# P_B_Jan_2018.net
KiCad netlist of a schematic drawn in EAGLE
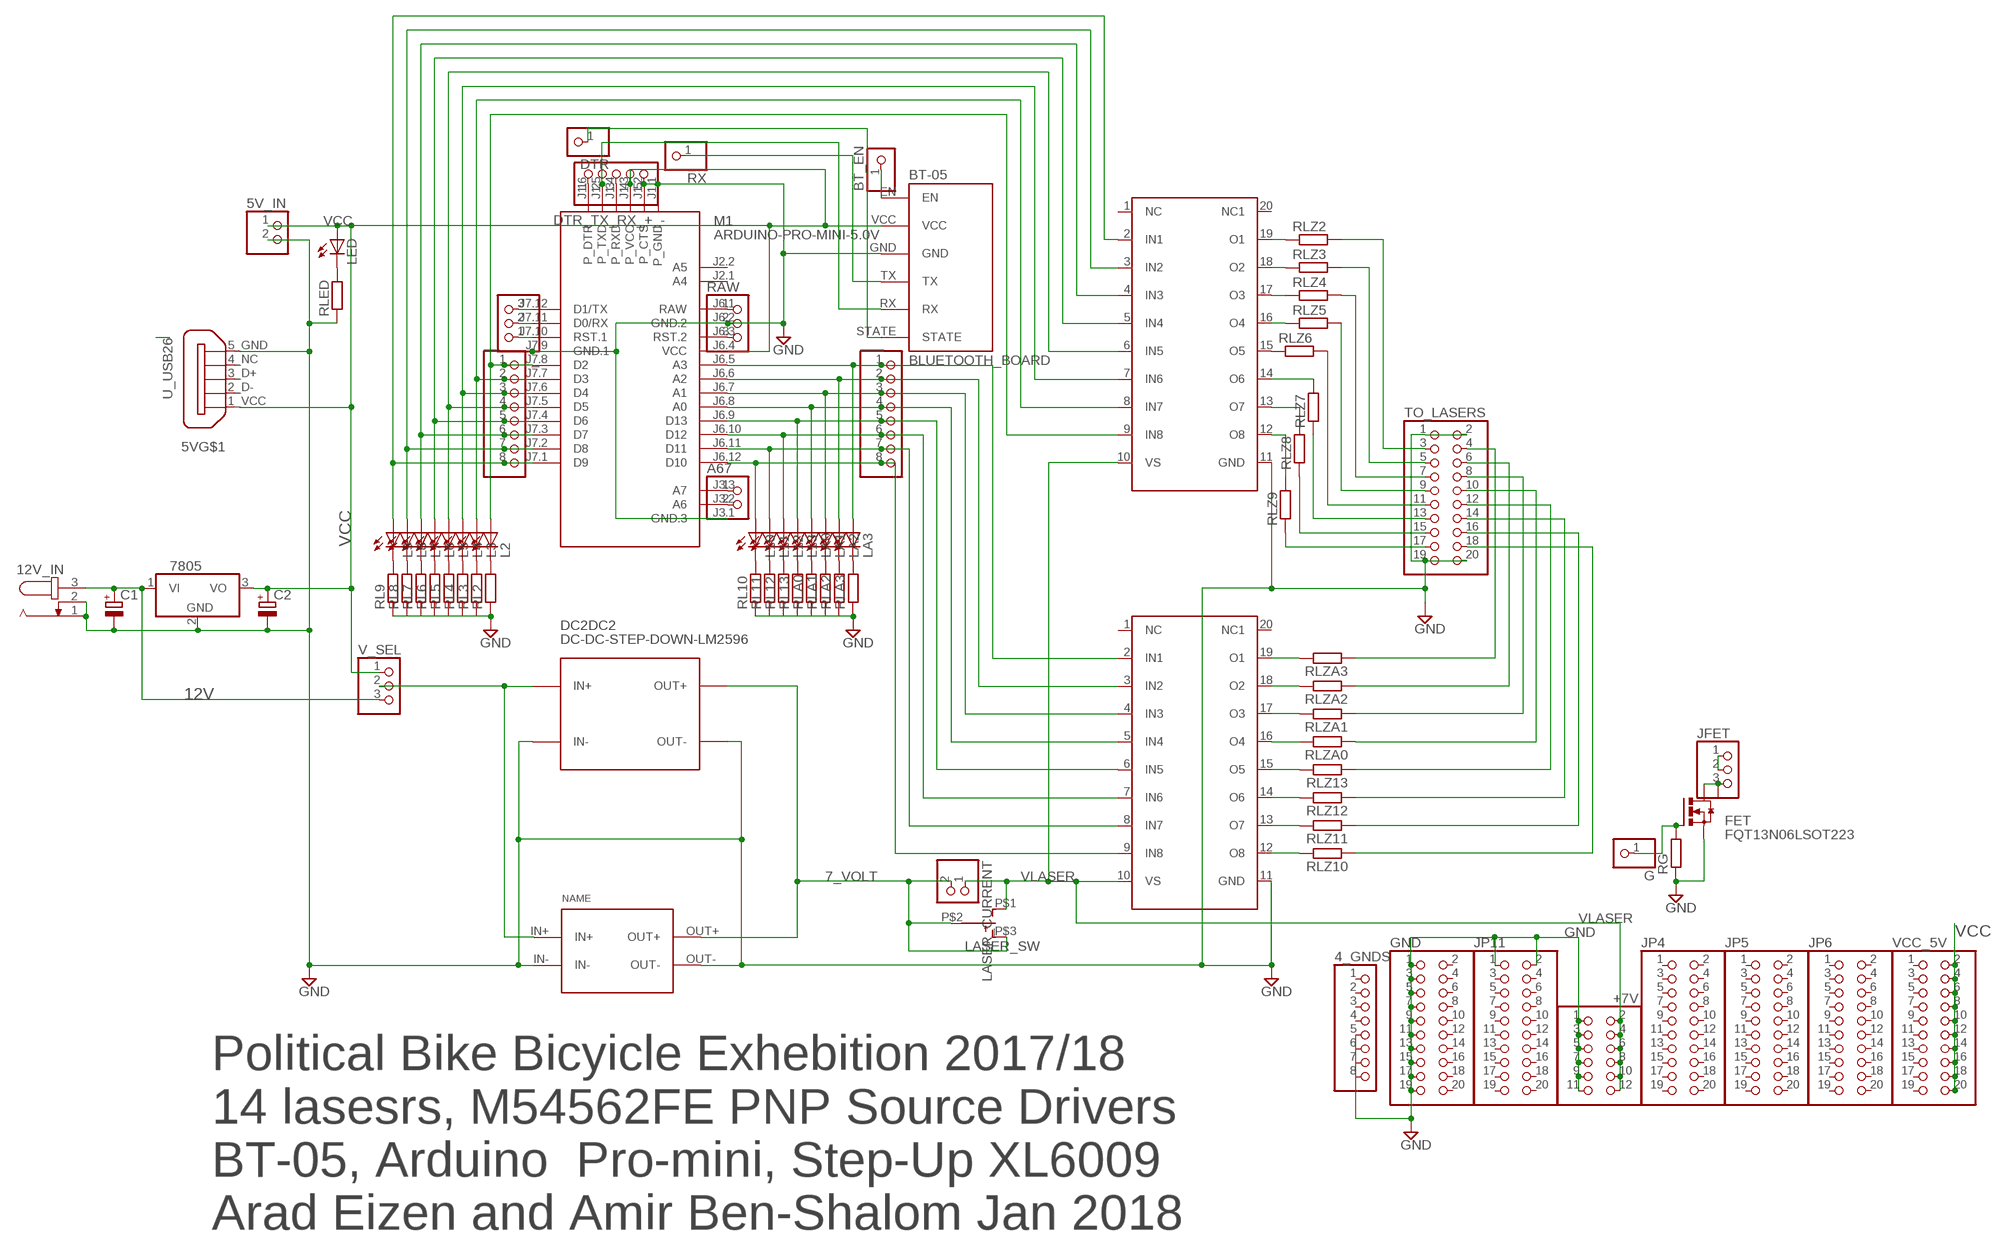
[diagram p0: schematic, sheet 1]

(export (version "E")
  (design (tool "Eeschema 10.0.6"))
  (components
    (comp (ref "+7V")
      (value "PINHD-2X6")
      (footprint "eagle-import:2X06")
      (libsource (lib "eagle-import") (part "PINHD-2X6"))
    )
    (comp (ref "4_GNDS")
      (value "PINHD-1X8")
      (footprint "eagle-import:1X08")
      (libsource (lib "eagle-import") (part "PINHD-1X8"))
    )
    (comp (ref "5V")
      (value "U_USB26")
      (footprint "eagle-import:U_USB_26")
      (libsource (lib "eagle-import") (part "U_USB26"))
    )
    (comp (ref "5V_IN")
      (value "PINHD-1X2SQ&RND")
      (footprint "eagle-import:1X02_SQ&ROUND")
      (libsource (lib "eagle-import") (part "Amir_May_15_for_Copy_only_PINHD-1X2SQ&RND"))
    )
    (comp (ref "12V_IN")
      (value "JACK-PLUGHOLE_PAD")
      (footprint "eagle-import:JACK_DC")
      (libsource (lib "eagle-import") (part "JACK-PLUGHOLE_PAD"))
    )
    (comp (ref "7805")
      (value "7805TV")
      (footprint "eagle-import:TO220V")
      (libsource (lib "eagle-import") (part "78TV05"))
    )
    (comp (ref "A67")
      (value "PINHD-1X2ROUND_PAD")
      (footprint "eagle-import:1X02_ROUND_PAD")
      (libsource (lib "eagle-import") (part "Amir_May_15_for_Copy_only_PINHD-1X2ROUND_PAD"))
    )
    (comp (ref "BT-05")
      (value "BLUETOOTH_BOARD")
      (footprint "eagle-import:BT_BOARD_FOOTPRINT")
      (libsource (lib "eagle-import") (part "BLUETOOTH_BOARD"))
    )
    (comp (ref "BT_EN")
      (value "PINHD-1X1")
      (footprint "eagle-import:1X01")
      (libsource (lib "eagle-import") (part "PINHD-1X1"))
    )
    (comp (ref "C1")
      (value "CPOL-EUE3.5-10")
      (footprint "eagle-import:E3,5-10")
      (libsource (lib "eagle-import") (part "CPOL-EUE3.5-10"))
    )
    (comp (ref "C2")
      (value "CPOL-EUE2.5-6")
      (footprint "eagle-import:E2,5-6")
      (libsource (lib "eagle-import") (part "CPOL-EUE2.5-6"))
    )
    (comp (ref "DC2DC")
      (value "DC2DC_CP8-ADJ")
      (footprint "eagle-import:CP8-ADJ")
      (libsource (lib "eagle-import") (part "DC2DC_CP8-ADJ"))
    )
    (comp (ref "DC2DC2")
      (value "DC-DC-STEP-DOWN-LM2596")
      (footprint "eagle-import:DC-DC-STEP-DOWN-LM2596")
      (libsource (lib "eagle-import") (part "DC-DC-STEP-DOWN-LM2596"))
    )
    (comp (ref "DTR")
      (value "PINHD-1X1")
      (footprint "eagle-import:1X01")
      (libsource (lib "eagle-import") (part "PINHD-1X1"))
    )
    (comp (ref "DTR_TX_RX_+_-")
      (value "PINHD-1X5")
      (footprint "eagle-import:1X05")
      (libsource (lib "eagle-import") (part "PINHD-1X5"))
    )
    (comp (ref "FET")
      (value "FQT13N06LSOT223")
      (footprint "eagle-import:SOT223")
      (libsource (lib "eagle-import") (part "FQT13N06LSOT223"))
    )
    (comp (ref "G")
      (value "PINHD-1X1")
      (footprint "eagle-import:1X01")
      (libsource (lib "eagle-import") (part "PINHD-1X1"))
    )
    (comp (ref "GND")
      (value "PINHD-2X10")
      (footprint "eagle-import:2X10")
      (libsource (lib "eagle-import") (part "PINHD-2X10"))
    )
    (comp (ref "JFET")
      (value "PIN_HEAD_1X3_MARKED2.56")
      (footprint "eagle-import:1X3_MARKED")
      (libsource (lib "eagle-import") (part "PIN_HEAD_1X3_MARKED2.56"))
    )
    (comp (ref "JP4")
      (value "PINHD-2X10")
      (footprint "eagle-import:2X10")
      (libsource (lib "eagle-import") (part "PINHD-2X10"))
    )
    (comp (ref "JP5")
      (value "PINHD-2X10")
      (footprint "eagle-import:2X10")
      (libsource (lib "eagle-import") (part "PINHD-2X10"))
    )
    (comp (ref "JP6")
      (value "PINHD-2X10")
      (footprint "eagle-import:2X10")
      (libsource (lib "eagle-import") (part "PINHD-2X10"))
    )
    (comp (ref "JP11")
      (value "PINHD-2X10")
      (footprint "eagle-import:2X10")
      (libsource (lib "eagle-import") (part "PINHD-2X10"))
    )
    (comp (ref "L2")
      (value "LEDCHIPLED_1206")
      (footprint "eagle-import:CHIPLED_1206")
      (libsource (lib "eagle-import") (part "LEDCHIPLED_1206"))
    )
    (comp (ref "L3")
      (value "LEDCHIPLED_1206")
      (footprint "eagle-import:CHIPLED_1206")
      (libsource (lib "eagle-import") (part "LEDCHIPLED_1206"))
    )
    (comp (ref "L4")
      (value "LEDCHIPLED_1206")
      (footprint "eagle-import:CHIPLED_1206")
      (libsource (lib "eagle-import") (part "LEDCHIPLED_1206"))
    )
    (comp (ref "L5")
      (value "LEDCHIPLED_1206")
      (footprint "eagle-import:CHIPLED_1206")
      (libsource (lib "eagle-import") (part "LEDCHIPLED_1206"))
    )
    (comp (ref "L6")
      (value "LEDCHIPLED_1206")
      (footprint "eagle-import:CHIPLED_1206")
      (libsource (lib "eagle-import") (part "LEDCHIPLED_1206"))
    )
    (comp (ref "L7")
      (value "LEDCHIPLED_1206")
      (footprint "eagle-import:CHIPLED_1206")
      (libsource (lib "eagle-import") (part "LEDCHIPLED_1206"))
    )
    (comp (ref "L8")
      (value "LEDCHIPLED_1206")
      (footprint "eagle-import:CHIPLED_1206")
      (libsource (lib "eagle-import") (part "LEDCHIPLED_1206"))
    )
    (comp (ref "L9")
      (value "LEDCHIPLED_1206")
      (footprint "eagle-import:CHIPLED_1206")
      (libsource (lib "eagle-import") (part "LEDCHIPLED_1206"))
    )
    (comp (ref "L10")
      (value "LEDCHIPLED_1206")
      (footprint "eagle-import:CHIPLED_1206")
      (libsource (lib "eagle-import") (part "LEDCHIPLED_1206"))
    )
    (comp (ref "L11")
      (value "LEDCHIPLED_1206")
      (footprint "eagle-import:CHIPLED_1206")
      (libsource (lib "eagle-import") (part "LEDCHIPLED_1206"))
    )
    (comp (ref "L12")
      (value "LEDCHIPLED_1206")
      (footprint "eagle-import:CHIPLED_1206")
      (libsource (lib "eagle-import") (part "LEDCHIPLED_1206"))
    )
    (comp (ref "L13")
      (value "LEDCHIPLED_1206")
      (footprint "eagle-import:CHIPLED_1206")
      (libsource (lib "eagle-import") (part "LEDCHIPLED_1206"))
    )
    (comp (ref "LA0")
      (value "LEDCHIPLED_1206")
      (footprint "eagle-import:CHIPLED_1206")
      (libsource (lib "eagle-import") (part "LEDCHIPLED_1206"))
    )
    (comp (ref "LA1")
      (value "LEDCHIPLED_1206")
      (footprint "eagle-import:CHIPLED_1206")
      (libsource (lib "eagle-import") (part "LEDCHIPLED_1206"))
    )
    (comp (ref "LA2")
      (value "LEDCHIPLED_1206")
      (footprint "eagle-import:CHIPLED_1206")
      (libsource (lib "eagle-import") (part "LEDCHIPLED_1206"))
    )
    (comp (ref "LA3")
      (value "LEDCHIPLED_1206")
      (footprint "eagle-import:CHIPLED_1206")
      (libsource (lib "eagle-import") (part "LEDCHIPLED_1206"))
    )
    (comp (ref "LASER_CURRENT")
      (value "PINHD-1X2ROUND_PAD")
      (footprint "eagle-import:1X02_ROUND_PAD")
      (libsource (lib "eagle-import") (part "PINHD-1X2ROUND_PAD"))
    )
    (comp (ref "LASER_SW")
      (value "SW_SPDTSS_12D_00_W")
      (footprint "eagle-import:SS_12D_00_W")
      (libsource (lib "eagle-import") (part "SW_SPDTSS_12D_00_W"))
    )
    (comp (ref "LED")
      (value "LED3MM")
      (footprint "eagle-import:LED3MM")
      (libsource (lib "eagle-import") (part "LED3MM"))
    )
    (comp (ref "M1")
      (value "ARDUINO-PRO-MINI-5.0V")
      (footprint "eagle-import:ARDUINO-PRO-MINI")
      (libsource (lib "eagle-import") (part "ARDUINO-PRO-MINI-5.0V"))
    )
    (comp (ref "RAW")
      (value "PINHD-1X3")
      (footprint "eagle-import:1X03")
      (libsource (lib "eagle-import") (part "PINHD-1X3"))
    )
    (comp (ref "RG")
      (value "R-EU_R0603")
      (footprint "eagle-import:R0603")
      (libsource (lib "eagle-import") (part "R-EU_R0603"))
    )
    (comp (ref "RL2")
      (value "R-EU_R0603")
      (footprint "eagle-import:R0603")
      (libsource (lib "eagle-import") (part "R-EU_R0603"))
    )
    (comp (ref "RL3")
      (value "R-EU_R0603")
      (footprint "eagle-import:R0603")
      (libsource (lib "eagle-import") (part "R-EU_R0603"))
    )
    (comp (ref "RL4")
      (value "R-EU_R0603")
      (footprint "eagle-import:R0603")
      (libsource (lib "eagle-import") (part "R-EU_R0603"))
    )
    (comp (ref "RL5")
      (value "R-EU_R0603")
      (footprint "eagle-import:R0603")
      (libsource (lib "eagle-import") (part "R-EU_R0603"))
    )
    (comp (ref "RL6")
      (value "R-EU_R0603")
      (footprint "eagle-import:R0603")
      (libsource (lib "eagle-import") (part "R-EU_R0603"))
    )
    (comp (ref "RL7")
      (value "R-EU_R0603")
      (footprint "eagle-import:R0603")
      (libsource (lib "eagle-import") (part "R-EU_R0603"))
    )
    (comp (ref "RL8")
      (value "R-EU_R0603")
      (footprint "eagle-import:R0603")
      (libsource (lib "eagle-import") (part "R-EU_R0603"))
    )
    (comp (ref "RL9")
      (value "R-EU_R0603")
      (footprint "eagle-import:R0603")
      (libsource (lib "eagle-import") (part "R-EU_R0603"))
    )
    (comp (ref "RL10")
      (value "R-EU_R0603")
      (footprint "eagle-import:R0603")
      (libsource (lib "eagle-import") (part "R-EU_R0603"))
    )
    (comp (ref "RL11")
      (value "R-EU_R0603")
      (footprint "eagle-import:R0603")
      (libsource (lib "eagle-import") (part "R-EU_R0603"))
    )
    (comp (ref "RL12")
      (value "R-EU_R0603")
      (footprint "eagle-import:R0603")
      (libsource (lib "eagle-import") (part "R-EU_R0603"))
    )
    (comp (ref "RL13")
      (value "R-EU_R0603")
      (footprint "eagle-import:R0603")
      (libsource (lib "eagle-import") (part "R-EU_R0603"))
    )
    (comp (ref "RLA0")
      (value "R-EU_R0603")
      (footprint "eagle-import:R0603")
      (libsource (lib "eagle-import") (part "R-EU_R0603"))
    )
    (comp (ref "RLA1")
      (value "R-EU_R0603")
      (footprint "eagle-import:R0603")
      (libsource (lib "eagle-import") (part "R-EU_R0603"))
    )
    (comp (ref "RLA2")
      (value "R-EU_R0603")
      (footprint "eagle-import:R0603")
      (libsource (lib "eagle-import") (part "R-EU_R0603"))
    )
    (comp (ref "RLA3")
      (value "R-EU_R0603")
      (footprint "eagle-import:R0603")
      (libsource (lib "eagle-import") (part "R-EU_R0603"))
    )
    (comp (ref "RLED")
      (value "R-EU_R0603")
      (footprint "eagle-import:R0603")
      (libsource (lib "eagle-import") (part "R-EU_R0603"))
    )
    (comp (ref "RLZ2")
      (value "R-EU_R0603")
      (footprint "eagle-import:R0603")
      (libsource (lib "eagle-import") (part "R-EU_R0603"))
    )
    (comp (ref "RLZ3")
      (value "R-EU_R0603")
      (footprint "eagle-import:R0603")
      (libsource (lib "eagle-import") (part "R-EU_R0603"))
    )
    (comp (ref "RLZ4")
      (value "R-EU_R0603")
      (footprint "eagle-import:R0603")
      (libsource (lib "eagle-import") (part "R-EU_R0603"))
    )
    (comp (ref "RLZ5")
      (value "R-EU_R0603")
      (footprint "eagle-import:R0603")
      (libsource (lib "eagle-import") (part "R-EU_R0603"))
    )
    (comp (ref "RLZ6")
      (value "R-EU_R0603")
      (footprint "eagle-import:R0603")
      (libsource (lib "eagle-import") (part "R-EU_R0603"))
    )
    (comp (ref "RLZ7")
      (value "R-EU_R0603")
      (footprint "eagle-import:R0603")
      (libsource (lib "eagle-import") (part "R-EU_R0603"))
    )
    (comp (ref "RLZ8")
      (value "R-EU_R0603")
      (footprint "eagle-import:R0603")
      (libsource (lib "eagle-import") (part "R-EU_R0603"))
    )
    (comp (ref "RLZ9")
      (value "R-EU_R0603")
      (footprint "eagle-import:R0603")
      (libsource (lib "eagle-import") (part "R-EU_R0603"))
    )
    (comp (ref "RLZ10")
      (value "R-EU_R0603")
      (footprint "eagle-import:R0603")
      (libsource (lib "eagle-import") (part "R-EU_R0603"))
    )
    (comp (ref "RLZ11")
      (value "R-EU_R0603")
      (footprint "eagle-import:R0603")
      (libsource (lib "eagle-import") (part "R-EU_R0603"))
    )
    (comp (ref "RLZ12")
      (value "R-EU_R0603")
      (footprint "eagle-import:R0603")
      (libsource (lib "eagle-import") (part "R-EU_R0603"))
    )
    (comp (ref "RLZ13")
      (value "R-EU_R0603")
      (footprint "eagle-import:R0603")
      (libsource (lib "eagle-import") (part "R-EU_R0603"))
    )
    (comp (ref "RLZA0")
      (value "R-EU_R0603")
      (footprint "eagle-import:R0603")
      (libsource (lib "eagle-import") (part "R-EU_R0603"))
    )
    (comp (ref "RLZA1")
      (value "R-EU_R0603")
      (footprint "eagle-import:R0603")
      (libsource (lib "eagle-import") (part "R-EU_R0603"))
    )
    (comp (ref "RLZA2")
      (value "R-EU_R0603")
      (footprint "eagle-import:R0603")
      (libsource (lib "eagle-import") (part "R-EU_R0603"))
    )
    (comp (ref "RLZA3")
      (value "R-EU_R0603")
      (footprint "eagle-import:R0603")
      (libsource (lib "eagle-import") (part "R-EU_R0603"))
    )
    (comp (ref "RX")
      (value "PINHD-1X1")
      (footprint "eagle-import:1X01")
      (libsource (lib "eagle-import") (part "PINHD-1X1"))
    )
    (comp (ref "TO_LASERS")
      (value "PINHD-2X10")
      (footprint "eagle-import:2X10")
      (libsource (lib "eagle-import") (part "PINHD-2X10"))
    )
    (comp (ref "U$5")
      (value "M54562P-SOP-20")
      (footprint "eagle-import:P-SOP-20")
      (libsource (lib "eagle-import") (part "M54562P-SOP-20"))
    )
    (comp (ref "U$6")
      (value "M54562P-SOP-20")
      (footprint "eagle-import:P-SOP-20")
      (libsource (lib "eagle-import") (part "M54562P-SOP-20"))
    )
    (comp (ref "VCC_5V")
      (value "PINHD-2X10")
      (footprint "eagle-import:2X10")
      (libsource (lib "eagle-import") (part "PINHD-2X10"))
    )
    (comp (ref "V_SEL")
      (value "PIN_HEAD_1X3_MARKED2.56")
      (footprint "eagle-import:1X3_MARKED")
      (libsource (lib "eagle-import") (part "PIN_HEAD_1X3_MARKED2.56"))
    )
    (comp (ref "_")
      (value "PINHD-1X3")
      (footprint "eagle-import:1X03")
      (libsource (lib "eagle-import") (part "PINHD-1X3"))
    )
    (comp (ref "__")
      (value "PINHD-1X8")
      (footprint "eagle-import:1X08")
      (libsource (lib "eagle-import") (part "PINHD-1X8"))
    )
    (comp (ref "___")
      (value "PINHD-1X8")
      (footprint "eagle-import:1X08")
      (libsource (lib "eagle-import") (part "PINHD-1X8"))
    )
  )
  (nets
    (net (code "1") (name "/7_VOLT") (class "Default")
      (node (ref "DC2DC") (pin "OUT+") (pinfunction "OUT+_OUT+") (pintype "passive"))
      (node (ref "DC2DC2") (pin "OUT+") (pinfunction "OUT+_OUT+") (pintype "bidirectional"))
      (node (ref "LASER_CURRENT") (pin "2") (pinfunction "2_2") (pintype "passive"))
      (node (ref "LASER_SW") (pin "P$2") (pinfunction "P_P$2") (pintype "passive"))
      (node (ref "LASER_SW") (pin "P$3") (pinfunction "S_P$3") (pintype "passive"))
    )
    (net (code "2") (name "/12V") (class "Default")
      (node (ref "12V_IN") (pin "3") (pinfunction "3_3") (pintype "passive"))
      (node (ref "7805") (pin "1") (pinfunction "VI_1") (pintype "input"))
      (node (ref "C1") (pin "+") (pinfunction "+_+") (pintype "passive"))
      (node (ref "V_SEL") (pin "3") (pinfunction "3_3") (pintype "passive"))
    )
    (net (code "3") (name "/VCC") (class "Default")
      (node (ref "5V") (pin "1_VCC") (pinfunction "1_VDD_1_VCC") (pintype "passive"))
      (node (ref "5V_IN") (pin "1") (pinfunction "1_1") (pintype "passive"))
      (node (ref "7805") (pin "3") (pinfunction "VO_3") (pintype "passive"))
      (node (ref "BT-05") (pin "VCC") (pinfunction "VCC_VCC") (pintype "bidirectional"))
      (node (ref "C2") (pin "+") (pinfunction "+_+") (pintype "passive"))
      (node (ref "DTR_TX_RX_+_-") (pin "4") (pinfunction "4_4") (pintype "passive"))
      (node (ref "LED") (pin "A") (pinfunction "A_A") (pintype "passive"))
      (node (ref "M1") (pin "J1.3") (pinfunction "P_VCC_J1.3") (pintype "bidirectional"))
      (node (ref "M1") (pin "J6.4") (pinfunction "VCC_J6.4") (pintype "power_in"))
      (node (ref "VCC_5V") (pin "10") (pinfunction "10_10") (pintype "passive"))
      (node (ref "VCC_5V") (pin "12") (pinfunction "12_12") (pintype "passive"))
      (node (ref "VCC_5V") (pin "14") (pinfunction "14_14") (pintype "passive"))
      (node (ref "VCC_5V") (pin "16") (pinfunction "16_16") (pintype "passive"))
      (node (ref "VCC_5V") (pin "18") (pinfunction "18_18") (pintype "passive"))
      (node (ref "VCC_5V") (pin "2") (pinfunction "2_2") (pintype "passive"))
      (node (ref "VCC_5V") (pin "20") (pinfunction "20_20") (pintype "passive"))
      (node (ref "VCC_5V") (pin "4") (pinfunction "4_4") (pintype "passive"))
      (node (ref "VCC_5V") (pin "6") (pinfunction "6_6") (pintype "passive"))
      (node (ref "VCC_5V") (pin "8") (pinfunction "8_8") (pintype "passive"))
      (node (ref "V_SEL") (pin "1") (pinfunction "1_1") (pintype "passive"))
    )
    (net (code "4") (name "/VLASER") (class "Default")
      (node (ref "+7V") (pin "10") (pinfunction "10_10") (pintype "passive"))
      (node (ref "+7V") (pin "12") (pinfunction "12_12") (pintype "passive"))
      (node (ref "+7V") (pin "2") (pinfunction "2_2") (pintype "passive"))
      (node (ref "+7V") (pin "4") (pinfunction "4_4") (pintype "passive"))
      (node (ref "+7V") (pin "6") (pinfunction "6_6") (pintype "passive"))
      (node (ref "+7V") (pin "8") (pinfunction "8_8") (pintype "passive"))
      (node (ref "LASER_CURRENT") (pin "1") (pinfunction "1_1") (pintype "passive"))
      (node (ref "LASER_SW") (pin "P$1") (pinfunction "O_P$1") (pintype "passive"))
      (node (ref "U$5") (pin "10") (pinfunction "VS_10") (pintype "bidirectional"))
      (node (ref "U$6") (pin "10") (pinfunction "VS_10") (pintype "bidirectional"))
    )
    (net (code "5") (name "GND") (class "Default")
      (node (ref "+7V") (pin "1") (pinfunction "1_1") (pintype "passive"))
      (node (ref "+7V") (pin "11") (pinfunction "11_11") (pintype "passive"))
      (node (ref "+7V") (pin "3") (pinfunction "3_3") (pintype "passive"))
      (node (ref "+7V") (pin "5") (pinfunction "5_5") (pintype "passive"))
      (node (ref "+7V") (pin "7") (pinfunction "7_7") (pintype "passive"))
      (node (ref "+7V") (pin "9") (pinfunction "9_9") (pintype "passive"))
      (node (ref "12V_IN") (pin "1") (pinfunction "1_1") (pintype "passive"))
      (node (ref "12V_IN") (pin "2") (pinfunction "2_2") (pintype "passive"))
      (node (ref "4_GNDS") (pin "5") (pinfunction "5_5") (pintype "passive"))
      (node (ref "4_GNDS") (pin "6") (pinfunction "6_6") (pintype "passive"))
      (node (ref "4_GNDS") (pin "7") (pinfunction "7_7") (pintype "passive"))
      (node (ref "4_GNDS") (pin "8") (pinfunction "8_8") (pintype "passive"))
      (node (ref "5V") (pin "5_GND") (pinfunction "5_GND_5_GND") (pintype "passive"))
      (node (ref "5V_IN") (pin "2") (pinfunction "2_2") (pintype "passive"))
      (node (ref "7805") (pin "2") (pinfunction "GND_2") (pintype "passive"))
      (node (ref "BT-05") (pin "GND") (pinfunction "GND_GND") (pintype "bidirectional"))
      (node (ref "C1") (pin "-") (pinfunction "-_-") (pintype "passive"))
      (node (ref "C2") (pin "-") (pinfunction "-_-") (pintype "passive"))
      (node (ref "DC2DC") (pin "IN-") (pinfunction "IN-_IN-") (pintype "passive"))
      (node (ref "DC2DC") (pin "OUT-") (pinfunction "OUT-_OUT-") (pintype "passive"))
      (node (ref "DC2DC2") (pin "IN-") (pinfunction "IN-_IN-") (pintype "bidirectional"))
      (node (ref "DC2DC2") (pin "OUT-") (pinfunction "OUT-_OUT-") (pintype "bidirectional"))
      (node (ref "DTR_TX_RX_+_-") (pin "5") (pinfunction "5_5") (pintype "passive"))
      (node (ref "FET") (pin "3") (pinfunction "S_3") (pintype "passive"))
      (node (ref "GND") (pin "1") (pinfunction "1_1") (pintype "passive"))
      (node (ref "GND") (pin "11") (pinfunction "11_11") (pintype "passive"))
      (node (ref "GND") (pin "13") (pinfunction "13_13") (pintype "passive"))
      (node (ref "GND") (pin "15") (pinfunction "15_15") (pintype "passive"))
      (node (ref "GND") (pin "17") (pinfunction "17_17") (pintype "passive"))
      (node (ref "GND") (pin "19") (pinfunction "19_19") (pintype "passive"))
      (node (ref "GND") (pin "3") (pinfunction "3_3") (pintype "passive"))
      (node (ref "GND") (pin "5") (pinfunction "5_5") (pintype "passive"))
      (node (ref "GND") (pin "7") (pinfunction "7_7") (pintype "passive"))
      (node (ref "GND") (pin "9") (pinfunction "9_9") (pintype "passive"))
      (node (ref "JP11") (pin "1") (pinfunction "1_1") (pintype "passive"))
      (node (ref "JP11") (pin "2") (pinfunction "2_2") (pintype "passive"))
      (node (ref "M1") (pin "J1.1") (pinfunction "P_GND_J1.1") (pintype "bidirectional"))
      (node (ref "M1") (pin "J1.2") (pinfunction "P_CTS_J1.2") (pintype "bidirectional"))
      (node (ref "M1") (pin "J3.1") (pinfunction "GND.3_J3.1") (pintype "bidirectional"))
      (node (ref "M1") (pin "J6.2") (pinfunction "GND.2_J6.2") (pintype "power_in"))
      (node (ref "M1") (pin "J7.9") (pinfunction "GND.1_J7.9") (pintype "power_in"))
      (node (ref "RAW") (pin "2") (pinfunction "2_2") (pintype "passive"))
      (node (ref "RG") (pin "1") (pinfunction "1_1") (pintype "passive"))
      (node (ref "RL10") (pin "1") (pinfunction "1_1") (pintype "passive"))
      (node (ref "RL11") (pin "1") (pinfunction "1_1") (pintype "passive"))
      (node (ref "RL12") (pin "1") (pinfunction "1_1") (pintype "passive"))
      (node (ref "RL13") (pin "1") (pinfunction "1_1") (pintype "passive"))
      (node (ref "RL2") (pin "1") (pinfunction "1_1") (pintype "passive"))
      (node (ref "RL3") (pin "1") (pinfunction "1_1") (pintype "passive"))
      (node (ref "RL4") (pin "1") (pinfunction "1_1") (pintype "passive"))
      (node (ref "RL5") (pin "1") (pinfunction "1_1") (pintype "passive"))
      (node (ref "RL6") (pin "1") (pinfunction "1_1") (pintype "passive"))
      (node (ref "RL7") (pin "1") (pinfunction "1_1") (pintype "passive"))
      (node (ref "RL8") (pin "1") (pinfunction "1_1") (pintype "passive"))
      (node (ref "RL9") (pin "1") (pinfunction "1_1") (pintype "passive"))
      (node (ref "RLA0") (pin "1") (pinfunction "1_1") (pintype "passive"))
      (node (ref "RLA1") (pin "1") (pinfunction "1_1") (pintype "passive"))
      (node (ref "RLA2") (pin "1") (pinfunction "1_1") (pintype "passive"))
      (node (ref "RLA3") (pin "1") (pinfunction "1_1") (pintype "passive"))
      (node (ref "RLED") (pin "1") (pinfunction "1_1") (pintype "passive"))
      (node (ref "TO_LASERS") (pin "1") (pinfunction "1_1") (pintype "passive"))
      (node (ref "TO_LASERS") (pin "19") (pinfunction "19_19") (pintype "passive"))
      (node (ref "TO_LASERS") (pin "2") (pinfunction "2_2") (pintype "passive"))
      (node (ref "TO_LASERS") (pin "20") (pinfunction "20_20") (pintype "passive"))
      (node (ref "U$5") (pin "11") (pinfunction "GND_11") (pintype "bidirectional"))
      (node (ref "U$6") (pin "11") (pinfunction "GND_11") (pintype "bidirectional"))
    )
    (net (code "6") (name "Net-(BT-05-PadEN)") (class "Default")
      (node (ref "BT-05") (pin "EN") (pinfunction "EN_EN") (pintype "bidirectional"))
      (node (ref "BT_EN") (pin "1") (pinfunction "1_1") (pintype "passive"))
    )
    (net (code "7") (name "Net-(BT-05-PadSTATE)") (class "Default")
      (node (ref "BT-05") (pin "STATE") (pinfunction "STATE_STATE") (pintype "bidirectional"))
      (node (ref "DTR") (pin "1") (pinfunction "1_1") (pintype "passive"))
    )
    (net (code "8") (name "Net-(BT-05-PadTX)") (class "Default")
      (node (ref "BT-05") (pin "TX") (pinfunction "TX_TX") (pintype "bidirectional"))
      (node (ref "RX") (pin "1") (pinfunction "1_1") (pintype "passive"))
    )
    (net (code "9") (name "Net-(DC2DC-PadIN+)") (class "Default")
      (node (ref "DC2DC") (pin "IN+") (pinfunction "IN+_IN+") (pintype "passive"))
      (node (ref "DC2DC2") (pin "IN+") (pinfunction "IN+_IN+") (pintype "bidirectional"))
      (node (ref "V_SEL") (pin "2") (pinfunction "2_2") (pintype "passive"))
    )
    (net (code "10") (name "Net-(FET-D)") (class "Default")
      (node (ref "FET") (pin "2") (pinfunction "D_2") (pintype "passive"))
      (node (ref "FET") (pin "4") (pinfunction "D1_4") (pintype "passive"))
      (node (ref "JFET") (pin "3") (pinfunction "3_3") (pintype "passive"))
    )
    (net (code "11") (name "Net-(FET-G)") (class "Default")
      (node (ref "FET") (pin "1") (pinfunction "G_1") (pintype "passive"))
      (node (ref "G") (pin "1") (pinfunction "1_1") (pintype "passive"))
      (node (ref "RG") (pin "2") (pinfunction "2_2") (pintype "passive"))
    )
    (net (code "12") (name "Net-(JFET-Pad1)") (class "Default")
      (node (ref "JFET") (pin "1") (pinfunction "1_1") (pintype "passive"))
      (node (ref "JFET") (pin "2") (pinfunction "2_2") (pintype "passive"))
    )
    (net (code "13") (name "Net-(L2-PadC)") (class "Default")
      (node (ref "L2") (pin "C") (pinfunction "C_C") (pintype "passive"))
      (node (ref "RL2") (pin "2") (pinfunction "2_2") (pintype "passive"))
    )
    (net (code "14") (name "Net-(L3-PadC)") (class "Default")
      (node (ref "L3") (pin "C") (pinfunction "C_C") (pintype "passive"))
      (node (ref "RL3") (pin "2") (pinfunction "2_2") (pintype "passive"))
    )
    (net (code "15") (name "Net-(L4-PadC)") (class "Default")
      (node (ref "L4") (pin "C") (pinfunction "C_C") (pintype "passive"))
      (node (ref "RL4") (pin "2") (pinfunction "2_2") (pintype "passive"))
    )
    (net (code "16") (name "Net-(L5-PadC)") (class "Default")
      (node (ref "L5") (pin "C") (pinfunction "C_C") (pintype "passive"))
      (node (ref "RL5") (pin "2") (pinfunction "2_2") (pintype "passive"))
    )
    (net (code "17") (name "Net-(L6-PadC)") (class "Default")
      (node (ref "L6") (pin "C") (pinfunction "C_C") (pintype "passive"))
      (node (ref "RL6") (pin "2") (pinfunction "2_2") (pintype "passive"))
    )
    (net (code "18") (name "Net-(L7-PadC)") (class "Default")
      (node (ref "L7") (pin "C") (pinfunction "C_C") (pintype "passive"))
      (node (ref "RL7") (pin "2") (pinfunction "2_2") (pintype "passive"))
    )
    (net (code "19") (name "Net-(L8-PadC)") (class "Default")
      (node (ref "L8") (pin "C") (pinfunction "C_C") (pintype "passive"))
      (node (ref "RL8") (pin "2") (pinfunction "2_2") (pintype "passive"))
    )
    (net (code "20") (name "Net-(L9-PadC)") (class "Default")
      (node (ref "L9") (pin "C") (pinfunction "C_C") (pintype "passive"))
      (node (ref "RL9") (pin "2") (pinfunction "2_2") (pintype "passive"))
    )
    (net (code "21") (name "Net-(L10-PadC)") (class "Default")
      (node (ref "L10") (pin "C") (pinfunction "C_C") (pintype "passive"))
      (node (ref "RL10") (pin "2") (pinfunction "2_2") (pintype "passive"))
    )
    (net (code "22") (name "Net-(L11-PadC)") (class "Default")
      (node (ref "L11") (pin "C") (pinfunction "C_C") (pintype "passive"))
      (node (ref "RL11") (pin "2") (pinfunction "2_2") (pintype "passive"))
    )
    (net (code "23") (name "Net-(L12-PadC)") (class "Default")
      (node (ref "L12") (pin "C") (pinfunction "C_C") (pintype "passive"))
      (node (ref "RL12") (pin "2") (pinfunction "2_2") (pintype "passive"))
    )
    (net (code "24") (name "Net-(L13-PadC)") (class "Default")
      (node (ref "L13") (pin "C") (pinfunction "C_C") (pintype "passive"))
      (node (ref "RL13") (pin "2") (pinfunction "2_2") (pintype "passive"))
    )
    (net (code "25") (name "Net-(LA0-PadC)") (class "Default")
      (node (ref "LA0") (pin "C") (pinfunction "C_C") (pintype "passive"))
      (node (ref "RLA0") (pin "2") (pinfunction "2_2") (pintype "passive"))
    )
    (net (code "26") (name "Net-(LA1-PadC)") (class "Default")
      (node (ref "LA1") (pin "C") (pinfunction "C_C") (pintype "passive"))
      (node (ref "RLA1") (pin "2") (pinfunction "2_2") (pintype "passive"))
    )
    (net (code "27") (name "Net-(LA2-PadC)") (class "Default")
      (node (ref "LA2") (pin "C") (pinfunction "C_C") (pintype "passive"))
      (node (ref "RLA2") (pin "2") (pinfunction "2_2") (pintype "passive"))
    )
    (net (code "28") (name "Net-(LA3-PadC)") (class "Default")
      (node (ref "LA3") (pin "C") (pinfunction "C_C") (pintype "passive"))
      (node (ref "RLA3") (pin "2") (pinfunction "2_2") (pintype "passive"))
    )
    (net (code "29") (name "Net-(LED-C)") (class "Default")
      (node (ref "LED") (pin "K") (pinfunction "C_K") (pintype "passive"))
      (node (ref "RLED") (pin "2") (pinfunction "2_2") (pintype "passive"))
    )
    (net (code "30") (name "Net-(M1-A0)") (class "Default")
      (node (ref "LA0") (pin "A") (pinfunction "A_A") (pintype "passive"))
      (node (ref "M1") (pin "J6.8") (pinfunction "A0_J6.8") (pintype "bidirectional"))
      (node (ref "U$6") (pin "5") (pinfunction "IN4_5") (pintype "bidirectional"))
      (node (ref "___") (pin "4") (pinfunction "4_4") (pintype "passive"))
    )
    (net (code "31") (name "Net-(M1-A1)") (class "Default")
      (node (ref "LA1") (pin "A") (pinfunction "A_A") (pintype "passive"))
      (node (ref "M1") (pin "J6.7") (pinfunction "A1_J6.7") (pintype "bidirectional"))
      (node (ref "U$6") (pin "4") (pinfunction "IN3_4") (pintype "bidirectional"))
      (node (ref "___") (pin "3") (pinfunction "3_3") (pintype "passive"))
    )
    (net (code "32") (name "Net-(M1-A2)") (class "Default")
      (node (ref "LA2") (pin "A") (pinfunction "A_A") (pintype "passive"))
      (node (ref "M1") (pin "J6.6") (pinfunction "A2_J6.6") (pintype "bidirectional"))
      (node (ref "U$6") (pin "3") (pinfunction "IN2_3") (pintype "bidirectional"))
      (node (ref "___") (pin "2") (pinfunction "2_2") (pintype "passive"))
    )
    (net (code "33") (name "Net-(M1-A3)") (class "Default")
      (node (ref "LA3") (pin "A") (pinfunction "A_A") (pintype "passive"))
      (node (ref "M1") (pin "J6.5") (pinfunction "A3_J6.5") (pintype "bidirectional"))
      (node (ref "U$6") (pin "2") (pinfunction "IN1_2") (pintype "bidirectional"))
      (node (ref "___") (pin "1") (pinfunction "1_1") (pintype "passive"))
    )
    (net (code "34") (name "Net-(M1-A6)") (class "Default")
      (node (ref "A67") (pin "2") (pinfunction "2_2") (pintype "passive"))
      (node (ref "M1") (pin "J3.2") (pinfunction "A6_J3.2") (pintype "bidirectional"))
    )
    (net (code "35") (name "Net-(M1-A7)") (class "Default")
      (node (ref "A67") (pin "1") (pinfunction "1_1") (pintype "passive"))
      (node (ref "M1") (pin "J3.3") (pinfunction "A7_J3.3") (pintype "bidirectional"))
    )
    (net (code "36") (name "Net-(M1-D0{slash}RX)") (class "Default")
      (node (ref "M1") (pin "J7.11") (pinfunction "D0/RX_J7.11") (pintype "bidirectional"))
      (node (ref "_") (pin "2") (pinfunction "2_2") (pintype "passive"))
    )
    (net (code "37") (name "Net-(M1-D1{slash}TX)") (class "Default")
      (node (ref "M1") (pin "J7.12") (pinfunction "D1/TX_J7.12") (pintype "bidirectional"))
      (node (ref "_") (pin "3") (pinfunction "3_3") (pintype "passive"))
    )
    (net (code "38") (name "Net-(M1-D2)") (class "Default")
      (node (ref "L2") (pin "A") (pinfunction "A_A") (pintype "passive"))
      (node (ref "M1") (pin "J7.8") (pinfunction "D2_J7.8") (pintype "bidirectional"))
      (node (ref "U$5") (pin "9") (pinfunction "IN8_9") (pintype "bidirectional"))
      (node (ref "__") (pin "1") (pinfunction "1_1") (pintype "passive"))
    )
    (net (code "39") (name "Net-(M1-D3)") (class "Default")
      (node (ref "L3") (pin "A") (pinfunction "A_A") (pintype "passive"))
      (node (ref "M1") (pin "J7.7") (pinfunction "D3_J7.7") (pintype "bidirectional"))
      (node (ref "U$5") (pin "8") (pinfunction "IN7_8") (pintype "bidirectional"))
      (node (ref "__") (pin "2") (pinfunction "2_2") (pintype "passive"))
    )
    (net (code "40") (name "Net-(M1-D4)") (class "Default")
      (node (ref "L4") (pin "A") (pinfunction "A_A") (pintype "passive"))
      (node (ref "M1") (pin "J7.6") (pinfunction "D4_J7.6") (pintype "bidirectional"))
      (node (ref "U$5") (pin "7") (pinfunction "IN6_7") (pintype "bidirectional"))
      (node (ref "__") (pin "3") (pinfunction "3_3") (pintype "passive"))
    )
    (net (code "41") (name "Net-(M1-D5)") (class "Default")
      (node (ref "L5") (pin "A") (pinfunction "A_A") (pintype "passive"))
      (node (ref "M1") (pin "J7.5") (pinfunction "D5_J7.5") (pintype "bidirectional"))
      (node (ref "U$5") (pin "6") (pinfunction "IN5_6") (pintype "bidirectional"))
      (node (ref "__") (pin "4") (pinfunction "4_4") (pintype "passive"))
    )
    (net (code "42") (name "Net-(M1-D6)") (class "Default")
      (node (ref "L6") (pin "A") (pinfunction "A_A") (pintype "passive"))
      (node (ref "M1") (pin "J7.4") (pinfunction "D6_J7.4") (pintype "bidirectional"))
      (node (ref "U$5") (pin "5") (pinfunction "IN4_5") (pintype "bidirectional"))
      (node (ref "__") (pin "5") (pinfunction "5_5") (pintype "passive"))
    )
    (net (code "43") (name "Net-(M1-D7)") (class "Default")
      (node (ref "L7") (pin "A") (pinfunction "A_A") (pintype "passive"))
      (node (ref "M1") (pin "J7.3") (pinfunction "D7_J7.3") (pintype "bidirectional"))
      (node (ref "U$5") (pin "4") (pinfunction "IN3_4") (pintype "bidirectional"))
      (node (ref "__") (pin "6") (pinfunction "6_6") (pintype "passive"))
    )
    (net (code "44") (name "Net-(M1-D8)") (class "Default")
      (node (ref "L8") (pin "A") (pinfunction "A_A") (pintype "passive"))
      (node (ref "M1") (pin "J7.2") (pinfunction "D8_J7.2") (pintype "bidirectional"))
      (node (ref "U$5") (pin "3") (pinfunction "IN2_3") (pintype "bidirectional"))
      (node (ref "__") (pin "7") (pinfunction "7_7") (pintype "passive"))
    )
    (net (code "45") (name "Net-(M1-D9)") (class "Default")
      (node (ref "L9") (pin "A") (pinfunction "A_A") (pintype "passive"))
      (node (ref "M1") (pin "J7.1") (pinfunction "D9_J7.1") (pintype "bidirectional"))
      (node (ref "U$5") (pin "2") (pinfunction "IN1_2") (pintype "bidirectional"))
      (node (ref "__") (pin "8") (pinfunction "8_8") (pintype "passive"))
    )
    (net (code "46") (name "Net-(M1-D10)") (class "Default")
      (node (ref "L10") (pin "A") (pinfunction "A_A") (pintype "passive"))
      (node (ref "M1") (pin "J6.12") (pinfunction "D10_J6.12") (pintype "bidirectional"))
      (node (ref "U$6") (pin "9") (pinfunction "IN8_9") (pintype "bidirectional"))
      (node (ref "___") (pin "8") (pinfunction "8_8") (pintype "passive"))
    )
    (net (code "47") (name "Net-(M1-D11)") (class "Default")
      (node (ref "L11") (pin "A") (pinfunction "A_A") (pintype "passive"))
      (node (ref "M1") (pin "J6.11") (pinfunction "D11_J6.11") (pintype "bidirectional"))
      (node (ref "U$6") (pin "8") (pinfunction "IN7_8") (pintype "bidirectional"))
      (node (ref "___") (pin "7") (pinfunction "7_7") (pintype "passive"))
    )
    (net (code "48") (name "Net-(M1-D12)") (class "Default")
      (node (ref "L12") (pin "A") (pinfunction "A_A") (pintype "passive"))
      (node (ref "M1") (pin "J6.10") (pinfunction "D12_J6.10") (pintype "bidirectional"))
      (node (ref "U$6") (pin "7") (pinfunction "IN6_7") (pintype "bidirectional"))
      (node (ref "___") (pin "6") (pinfunction "6_6") (pintype "passive"))
    )
    (net (code "49") (name "Net-(M1-D13)") (class "Default")
      (node (ref "L13") (pin "A") (pinfunction "A_A") (pintype "passive"))
      (node (ref "M1") (pin "J6.9") (pinfunction "D13_J6.9") (pintype "bidirectional"))
      (node (ref "U$6") (pin "6") (pinfunction "IN5_6") (pintype "bidirectional"))
      (node (ref "___") (pin "5") (pinfunction "5_5") (pintype "passive"))
    )
    (net (code "50") (name "Net-(M1-P_DTR)") (class "Default")
      (node (ref "DTR_TX_RX_+_-") (pin "1") (pinfunction "1_1") (pintype "passive"))
      (node (ref "M1") (pin "J1.6") (pinfunction "P_DTR_J1.6") (pintype "bidirectional"))
    )
    (net (code "51") (name "Net-(M1-P_RXD)") (class "Default")
      (node (ref "DTR_TX_RX_+_-") (pin "3") (pinfunction "3_3") (pintype "passive"))
      (node (ref "M1") (pin "J1.4") (pinfunction "P_RXD_J1.4") (pintype "bidirectional"))
    )
    (net (code "52") (name "Net-(M1-P_TXD)") (class "Default")
      (node (ref "BT-05") (pin "RX") (pinfunction "RX_RX") (pintype "bidirectional"))
      (node (ref "DTR_TX_RX_+_-") (pin "2") (pinfunction "2_2") (pintype "passive"))
      (node (ref "M1") (pin "J1.5") (pinfunction "P_TXD_J1.5") (pintype "bidirectional"))
    )
    (net (code "53") (name "Net-(M1-RAW)") (class "Default")
      (node (ref "M1") (pin "J6.1") (pinfunction "RAW_J6.1") (pintype "power_in"))
      (node (ref "RAW") (pin "1") (pinfunction "1_1") (pintype "passive"))
    )
    (net (code "54") (name "Net-(M1-RST.1)") (class "Default")
      (node (ref "M1") (pin "J7.10") (pinfunction "RST.1_J7.10") (pintype "bidirectional"))
      (node (ref "_") (pin "1") (pinfunction "1_1") (pintype "passive"))
    )
    (net (code "55") (name "Net-(M1-RST.2)") (class "Default")
      (node (ref "M1") (pin "J6.3") (pinfunction "RST.2_J6.3") (pintype "bidirectional"))
      (node (ref "RAW") (pin "3") (pinfunction "3_3") (pintype "passive"))
    )
    (net (code "56") (name "Net-(RLZ2-Pad2)") (class "Default")
      (node (ref "RLZ2") (pin "2") (pinfunction "2_2") (pintype "passive"))
      (node (ref "TO_LASERS") (pin "3") (pinfunction "3_3") (pintype "passive"))
    )
    (net (code "57") (name "Net-(RLZ3-Pad2)") (class "Default")
      (node (ref "RLZ3") (pin "2") (pinfunction "2_2") (pintype "passive"))
      (node (ref "TO_LASERS") (pin "5") (pinfunction "5_5") (pintype "passive"))
    )
    (net (code "58") (name "Net-(RLZ4-Pad2)") (class "Default")
      (node (ref "RLZ4") (pin "2") (pinfunction "2_2") (pintype "passive"))
      (node (ref "TO_LASERS") (pin "7") (pinfunction "7_7") (pintype "passive"))
    )
    (net (code "59") (name "Net-(RLZ5-Pad2)") (class "Default")
      (node (ref "RLZ5") (pin "2") (pinfunction "2_2") (pintype "passive"))
      (node (ref "TO_LASERS") (pin "9") (pinfunction "9_9") (pintype "passive"))
    )
    (net (code "60") (name "Net-(RLZ6-Pad2)") (class "Default")
      (node (ref "RLZ6") (pin "2") (pinfunction "2_2") (pintype "passive"))
      (node (ref "TO_LASERS") (pin "11") (pinfunction "11_11") (pintype "passive"))
    )
    (net (code "61") (name "Net-(RLZ7-Pad1)") (class "Default")
      (node (ref "RLZ7") (pin "1") (pinfunction "1_1") (pintype "passive"))
      (node (ref "TO_LASERS") (pin "13") (pinfunction "13_13") (pintype "passive"))
    )
    (net (code "62") (name "Net-(RLZ8-Pad1)") (class "Default")
      (node (ref "RLZ8") (pin "1") (pinfunction "1_1") (pintype "passive"))
      (node (ref "TO_LASERS") (pin "15") (pinfunction "15_15") (pintype "passive"))
    )
    (net (code "63") (name "Net-(RLZ9-Pad1)") (class "Default")
      (node (ref "RLZ9") (pin "1") (pinfunction "1_1") (pintype "passive"))
      (node (ref "TO_LASERS") (pin "17") (pinfunction "17_17") (pintype "passive"))
    )
    (net (code "64") (name "Net-(RLZ10-Pad1)") (class "Default")
      (node (ref "RLZ10") (pin "1") (pinfunction "1_1") (pintype "passive"))
      (node (ref "TO_LASERS") (pin "18") (pinfunction "18_18") (pintype "passive"))
    )
    (net (code "65") (name "Net-(RLZ11-Pad1)") (class "Default")
      (node (ref "RLZ11") (pin "1") (pinfunction "1_1") (pintype "passive"))
      (node (ref "TO_LASERS") (pin "16") (pinfunction "16_16") (pintype "passive"))
    )
    (net (code "66") (name "Net-(RLZ12-Pad1)") (class "Default")
      (node (ref "RLZ12") (pin "1") (pinfunction "1_1") (pintype "passive"))
      (node (ref "TO_LASERS") (pin "14") (pinfunction "14_14") (pintype "passive"))
    )
    (net (code "67") (name "Net-(RLZ13-Pad1)") (class "Default")
      (node (ref "RLZ13") (pin "1") (pinfunction "1_1") (pintype "passive"))
      (node (ref "TO_LASERS") (pin "12") (pinfunction "12_12") (pintype "passive"))
    )
    (net (code "68") (name "Net-(RLZA0-Pad1)") (class "Default")
      (node (ref "RLZA0") (pin "1") (pinfunction "1_1") (pintype "passive"))
      (node (ref "TO_LASERS") (pin "10") (pinfunction "10_10") (pintype "passive"))
    )
    (net (code "69") (name "Net-(RLZA1-Pad1)") (class "Default")
      (node (ref "RLZA1") (pin "1") (pinfunction "1_1") (pintype "passive"))
      (node (ref "TO_LASERS") (pin "8") (pinfunction "8_8") (pintype "passive"))
    )
    (net (code "70") (name "Net-(RLZA2-Pad1)") (class "Default")
      (node (ref "RLZA2") (pin "1") (pinfunction "1_1") (pintype "passive"))
      (node (ref "TO_LASERS") (pin "6") (pinfunction "6_6") (pintype "passive"))
    )
    (net (code "71") (name "Net-(RLZA3-Pad1)") (class "Default")
      (node (ref "RLZA3") (pin "1") (pinfunction "1_1") (pintype "passive"))
      (node (ref "TO_LASERS") (pin "4") (pinfunction "4_4") (pintype "passive"))
    )
    (net (code "72") (name "Net-(U$5-O1)") (class "Default")
      (node (ref "RLZ2") (pin "1") (pinfunction "1_1") (pintype "passive"))
      (node (ref "U$5") (pin "19") (pinfunction "O1_19") (pintype "bidirectional"))
    )
    (net (code "73") (name "Net-(U$5-O2)") (class "Default")
      (node (ref "RLZ3") (pin "1") (pinfunction "1_1") (pintype "passive"))
      (node (ref "U$5") (pin "18") (pinfunction "O2_18") (pintype "bidirectional"))
    )
    (net (code "74") (name "Net-(U$5-O3)") (class "Default")
      (node (ref "RLZ4") (pin "1") (pinfunction "1_1") (pintype "passive"))
      (node (ref "U$5") (pin "17") (pinfunction "O3_17") (pintype "bidirectional"))
    )
    (net (code "75") (name "Net-(U$5-O4)") (class "Default")
      (node (ref "RLZ5") (pin "1") (pinfunction "1_1") (pintype "passive"))
      (node (ref "U$5") (pin "16") (pinfunction "O4_16") (pintype "bidirectional"))
    )
    (net (code "76") (name "Net-(U$5-O5)") (class "Default")
      (node (ref "RLZ6") (pin "1") (pinfunction "1_1") (pintype "passive"))
      (node (ref "U$5") (pin "15") (pinfunction "O5_15") (pintype "bidirectional"))
    )
    (net (code "77") (name "Net-(U$5-O6)") (class "Default")
      (node (ref "RLZ7") (pin "2") (pinfunction "2_2") (pintype "passive"))
      (node (ref "U$5") (pin "14") (pinfunction "O6_14") (pintype "bidirectional"))
    )
    (net (code "78") (name "Net-(U$5-O7)") (class "Default")
      (node (ref "RLZ8") (pin "2") (pinfunction "2_2") (pintype "passive"))
      (node (ref "U$5") (pin "13") (pinfunction "O7_13") (pintype "bidirectional"))
    )
    (net (code "79") (name "Net-(U$5-O8)") (class "Default")
      (node (ref "RLZ9") (pin "2") (pinfunction "2_2") (pintype "passive"))
      (node (ref "U$5") (pin "12") (pinfunction "O8_12") (pintype "bidirectional"))
    )
    (net (code "80") (name "Net-(U$6-O1)") (class "Default")
      (node (ref "RLZA3") (pin "2") (pinfunction "2_2") (pintype "passive"))
      (node (ref "U$6") (pin "19") (pinfunction "O1_19") (pintype "bidirectional"))
    )
    (net (code "81") (name "Net-(U$6-O2)") (class "Default")
      (node (ref "RLZA2") (pin "2") (pinfunction "2_2") (pintype "passive"))
      (node (ref "U$6") (pin "18") (pinfunction "O2_18") (pintype "bidirectional"))
    )
    (net (code "82") (name "Net-(U$6-O3)") (class "Default")
      (node (ref "RLZA1") (pin "2") (pinfunction "2_2") (pintype "passive"))
      (node (ref "U$6") (pin "17") (pinfunction "O3_17") (pintype "bidirectional"))
    )
    (net (code "83") (name "Net-(U$6-O4)") (class "Default")
      (node (ref "RLZA0") (pin "2") (pinfunction "2_2") (pintype "passive"))
      (node (ref "U$6") (pin "16") (pinfunction "O4_16") (pintype "bidirectional"))
    )
    (net (code "84") (name "Net-(U$6-O5)") (class "Default")
      (node (ref "RLZ13") (pin "2") (pinfunction "2_2") (pintype "passive"))
      (node (ref "U$6") (pin "15") (pinfunction "O5_15") (pintype "bidirectional"))
    )
    (net (code "85") (name "Net-(U$6-O6)") (class "Default")
      (node (ref "RLZ12") (pin "2") (pinfunction "2_2") (pintype "passive"))
      (node (ref "U$6") (pin "14") (pinfunction "O6_14") (pintype "bidirectional"))
    )
    (net (code "86") (name "Net-(U$6-O7)") (class "Default")
      (node (ref "RLZ11") (pin "2") (pinfunction "2_2") (pintype "passive"))
      (node (ref "U$6") (pin "13") (pinfunction "O7_13") (pintype "bidirectional"))
    )
    (net (code "87") (name "Net-(U$6-O8)") (class "Default")
      (node (ref "RLZ10") (pin "2") (pinfunction "2_2") (pintype "passive"))
      (node (ref "U$6") (pin "12") (pinfunction "O8_12") (pintype "bidirectional"))
    )
    (net (code "88") (name "unconnected-(4_GNDS-Pad1)") (class "Default")
      (node (ref "4_GNDS") (pin "1") (pinfunction "1_1") (pintype "passive"))
    )
    (net (code "89") (name "unconnected-(4_GNDS-Pad2)") (class "Default")
      (node (ref "4_GNDS") (pin "2") (pinfunction "2_2") (pintype "passive"))
    )
    (net (code "90") (name "unconnected-(4_GNDS-Pad3)") (class "Default")
      (node (ref "4_GNDS") (pin "3") (pinfunction "3_3") (pintype "passive"))
    )
    (net (code "91") (name "unconnected-(4_GNDS-Pad4)") (class "Default")
      (node (ref "4_GNDS") (pin "4") (pinfunction "4_4") (pintype "passive"))
    )
    (net (code "92") (name "unconnected-(5V-Pad2_D-)") (class "Default")
      (node (ref "5V") (pin "2_D-") (pinfunction "2_D-_2_D-") (pintype "passive"))
    )
    (net (code "93") (name "unconnected-(5V-Pad3_D+)") (class "Default")
      (node (ref "5V") (pin "3_D+") (pinfunction "3_D+_3_D+") (pintype "passive"))
    )
    (net (code "94") (name "unconnected-(5V-Pad4_NC)") (class "Default")
      (node (ref "5V") (pin "4_NC") (pinfunction "4_NC_4_NC") (pintype "passive"))
    )
    (net (code "95") (name "unconnected-(GND-Pad2)") (class "Default")
      (node (ref "GND") (pin "2") (pinfunction "2_2") (pintype "passive"))
    )
    (net (code "96") (name "unconnected-(GND-Pad4)") (class "Default")
      (node (ref "GND") (pin "4") (pinfunction "4_4") (pintype "passive"))
    )
    (net (code "97") (name "unconnected-(GND-Pad6)") (class "Default")
      (node (ref "GND") (pin "6") (pinfunction "6_6") (pintype "passive"))
    )
    (net (code "98") (name "unconnected-(GND-Pad8)") (class "Default")
      (node (ref "GND") (pin "8") (pinfunction "8_8") (pintype "passive"))
    )
    (net (code "99") (name "unconnected-(GND-Pad10)") (class "Default")
      (node (ref "GND") (pin "10") (pinfunction "10_10") (pintype "passive"))
    )
    (net (code "100") (name "unconnected-(GND-Pad12)") (class "Default")
      (node (ref "GND") (pin "12") (pinfunction "12_12") (pintype "passive"))
    )
    (net (code "101") (name "unconnected-(GND-Pad14)") (class "Default")
      (node (ref "GND") (pin "14") (pinfunction "14_14") (pintype "passive"))
    )
    (net (code "102") (name "unconnected-(GND-Pad16)") (class "Default")
      (node (ref "GND") (pin "16") (pinfunction "16_16") (pintype "passive"))
    )
    (net (code "103") (name "unconnected-(GND-Pad18)") (class "Default")
      (node (ref "GND") (pin "18") (pinfunction "18_18") (pintype "passive"))
    )
    (net (code "104") (name "unconnected-(GND-Pad20)") (class "Default")
      (node (ref "GND") (pin "20") (pinfunction "20_20") (pintype "passive"))
    )
    (net (code "105") (name "unconnected-(JP4-Pad1)") (class "Default")
      (node (ref "JP4") (pin "1") (pinfunction "1_1") (pintype "passive"))
    )
    (net (code "106") (name "unconnected-(JP4-Pad2)") (class "Default")
      (node (ref "JP4") (pin "2") (pinfunction "2_2") (pintype "passive"))
    )
    (net (code "107") (name "unconnected-(JP4-Pad3)") (class "Default")
      (node (ref "JP4") (pin "3") (pinfunction "3_3") (pintype "passive"))
    )
    (net (code "108") (name "unconnected-(JP4-Pad4)") (class "Default")
      (node (ref "JP4") (pin "4") (pinfunction "4_4") (pintype "passive"))
    )
    (net (code "109") (name "unconnected-(JP4-Pad5)") (class "Default")
      (node (ref "JP4") (pin "5") (pinfunction "5_5") (pintype "passive"))
    )
    (net (code "110") (name "unconnected-(JP4-Pad6)") (class "Default")
      (node (ref "JP4") (pin "6") (pinfunction "6_6") (pintype "passive"))
    )
    (net (code "111") (name "unconnected-(JP4-Pad7)") (class "Default")
      (node (ref "JP4") (pin "7") (pinfunction "7_7") (pintype "passive"))
    )
    (net (code "112") (name "unconnected-(JP4-Pad8)") (class "Default")
      (node (ref "JP4") (pin "8") (pinfunction "8_8") (pintype "passive"))
    )
    (net (code "113") (name "unconnected-(JP4-Pad9)") (class "Default")
      (node (ref "JP4") (pin "9") (pinfunction "9_9") (pintype "passive"))
    )
    (net (code "114") (name "unconnected-(JP4-Pad10)") (class "Default")
      (node (ref "JP4") (pin "10") (pinfunction "10_10") (pintype "passive"))
    )
    (net (code "115") (name "unconnected-(JP4-Pad11)") (class "Default")
      (node (ref "JP4") (pin "11") (pinfunction "11_11") (pintype "passive"))
    )
    (net (code "116") (name "unconnected-(JP4-Pad12)") (class "Default")
      (node (ref "JP4") (pin "12") (pinfunction "12_12") (pintype "passive"))
    )
    (net (code "117") (name "unconnected-(JP4-Pad13)") (class "Default")
      (node (ref "JP4") (pin "13") (pinfunction "13_13") (pintype "passive"))
    )
    (net (code "118") (name "unconnected-(JP4-Pad14)") (class "Default")
      (node (ref "JP4") (pin "14") (pinfunction "14_14") (pintype "passive"))
    )
    (net (code "119") (name "unconnected-(JP4-Pad15)") (class "Default")
      (node (ref "JP4") (pin "15") (pinfunction "15_15") (pintype "passive"))
    )
    (net (code "120") (name "unconnected-(JP4-Pad16)") (class "Default")
      (node (ref "JP4") (pin "16") (pinfunction "16_16") (pintype "passive"))
    )
    (net (code "121") (name "unconnected-(JP4-Pad17)") (class "Default")
      (node (ref "JP4") (pin "17") (pinfunction "17_17") (pintype "passive"))
    )
    (net (code "122") (name "unconnected-(JP4-Pad18)") (class "Default")
      (node (ref "JP4") (pin "18") (pinfunction "18_18") (pintype "passive"))
    )
    (net (code "123") (name "unconnected-(JP4-Pad19)") (class "Default")
      (node (ref "JP4") (pin "19") (pinfunction "19_19") (pintype "passive"))
    )
    (net (code "124") (name "unconnected-(JP4-Pad20)") (class "Default")
      (node (ref "JP4") (pin "20") (pinfunction "20_20") (pintype "passive"))
    )
    (net (code "125") (name "unconnected-(JP5-Pad1)") (class "Default")
      (node (ref "JP5") (pin "1") (pinfunction "1_1") (pintype "passive"))
    )
    (net (code "126") (name "unconnected-(JP5-Pad2)") (class "Default")
      (node (ref "JP5") (pin "2") (pinfunction "2_2") (pintype "passive"))
    )
    (net (code "127") (name "unconnected-(JP5-Pad3)") (class "Default")
      (node (ref "JP5") (pin "3") (pinfunction "3_3") (pintype "passive"))
    )
    (net (code "128") (name "unconnected-(JP5-Pad4)") (class "Default")
      (node (ref "JP5") (pin "4") (pinfunction "4_4") (pintype "passive"))
    )
    (net (code "129") (name "unconnected-(JP5-Pad5)") (class "Default")
      (node (ref "JP5") (pin "5") (pinfunction "5_5") (pintype "passive"))
    )
    (net (code "130") (name "unconnected-(JP5-Pad6)") (class "Default")
      (node (ref "JP5") (pin "6") (pinfunction "6_6") (pintype "passive"))
    )
    (net (code "131") (name "unconnected-(JP5-Pad7)") (class "Default")
      (node (ref "JP5") (pin "7") (pinfunction "7_7") (pintype "passive"))
    )
    (net (code "132") (name "unconnected-(JP5-Pad8)") (class "Default")
      (node (ref "JP5") (pin "8") (pinfunction "8_8") (pintype "passive"))
    )
    (net (code "133") (name "unconnected-(JP5-Pad9)") (class "Default")
      (node (ref "JP5") (pin "9") (pinfunction "9_9") (pintype "passive"))
    )
    (net (code "134") (name "unconnected-(JP5-Pad10)") (class "Default")
      (node (ref "JP5") (pin "10") (pinfunction "10_10") (pintype "passive"))
    )
    (net (code "135") (name "unconnected-(JP5-Pad11)") (class "Default")
      (node (ref "JP5") (pin "11") (pinfunction "11_11") (pintype "passive"))
    )
    (net (code "136") (name "unconnected-(JP5-Pad12)") (class "Default")
      (node (ref "JP5") (pin "12") (pinfunction "12_12") (pintype "passive"))
    )
    (net (code "137") (name "unconnected-(JP5-Pad13)") (class "Default")
      (node (ref "JP5") (pin "13") (pinfunction "13_13") (pintype "passive"))
    )
    (net (code "138") (name "unconnected-(JP5-Pad14)") (class "Default")
      (node (ref "JP5") (pin "14") (pinfunction "14_14") (pintype "passive"))
    )
    (net (code "139") (name "unconnected-(JP5-Pad15)") (class "Default")
      (node (ref "JP5") (pin "15") (pinfunction "15_15") (pintype "passive"))
    )
    (net (code "140") (name "unconnected-(JP5-Pad16)") (class "Default")
      (node (ref "JP5") (pin "16") (pinfunction "16_16") (pintype "passive"))
    )
    (net (code "141") (name "unconnected-(JP5-Pad17)") (class "Default")
      (node (ref "JP5") (pin "17") (pinfunction "17_17") (pintype "passive"))
    )
    (net (code "142") (name "unconnected-(JP5-Pad18)") (class "Default")
      (node (ref "JP5") (pin "18") (pinfunction "18_18") (pintype "passive"))
    )
    (net (code "143") (name "unconnected-(JP5-Pad19)") (class "Default")
      (node (ref "JP5") (pin "19") (pinfunction "19_19") (pintype "passive"))
    )
    (net (code "144") (name "unconnected-(JP5-Pad20)") (class "Default")
      (node (ref "JP5") (pin "20") (pinfunction "20_20") (pintype "passive"))
    )
    (net (code "145") (name "unconnected-(JP6-Pad1)") (class "Default")
      (node (ref "JP6") (pin "1") (pinfunction "1_1") (pintype "passive"))
    )
    (net (code "146") (name "unconnected-(JP6-Pad2)") (class "Default")
      (node (ref "JP6") (pin "2") (pinfunction "2_2") (pintype "passive"))
    )
    (net (code "147") (name "unconnected-(JP6-Pad3)") (class "Default")
      (node (ref "JP6") (pin "3") (pinfunction "3_3") (pintype "passive"))
    )
    (net (code "148") (name "unconnected-(JP6-Pad4)") (class "Default")
      (node (ref "JP6") (pin "4") (pinfunction "4_4") (pintype "passive"))
    )
    (net (code "149") (name "unconnected-(JP6-Pad5)") (class "Default")
      (node (ref "JP6") (pin "5") (pinfunction "5_5") (pintype "passive"))
    )
    (net (code "150") (name "unconnected-(JP6-Pad6)") (class "Default")
      (node (ref "JP6") (pin "6") (pinfunction "6_6") (pintype "passive"))
    )
    (net (code "151") (name "unconnected-(JP6-Pad7)") (class "Default")
      (node (ref "JP6") (pin "7") (pinfunction "7_7") (pintype "passive"))
    )
    (net (code "152") (name "unconnected-(JP6-Pad8)") (class "Default")
      (node (ref "JP6") (pin "8") (pinfunction "8_8") (pintype "passive"))
    )
    (net (code "153") (name "unconnected-(JP6-Pad9)") (class "Default")
      (node (ref "JP6") (pin "9") (pinfunction "9_9") (pintype "passive"))
    )
    (net (code "154") (name "unconnected-(JP6-Pad10)") (class "Default")
      (node (ref "JP6") (pin "10") (pinfunction "10_10") (pintype "passive"))
    )
    (net (code "155") (name "unconnected-(JP6-Pad11)") (class "Default")
      (node (ref "JP6") (pin "11") (pinfunction "11_11") (pintype "passive"))
    )
    (net (code "156") (name "unconnected-(JP6-Pad12)") (class "Default")
      (node (ref "JP6") (pin "12") (pinfunction "12_12") (pintype "passive"))
    )
    (net (code "157") (name "unconnected-(JP6-Pad13)") (class "Default")
      (node (ref "JP6") (pin "13") (pinfunction "13_13") (pintype "passive"))
    )
    (net (code "158") (name "unconnected-(JP6-Pad14)") (class "Default")
      (node (ref "JP6") (pin "14") (pinfunction "14_14") (pintype "passive"))
    )
    (net (code "159") (name "unconnected-(JP6-Pad15)") (class "Default")
      (node (ref "JP6") (pin "15") (pinfunction "15_15") (pintype "passive"))
    )
    (net (code "160") (name "unconnected-(JP6-Pad16)") (class "Default")
      (node (ref "JP6") (pin "16") (pinfunction "16_16") (pintype "passive"))
    )
    (net (code "161") (name "unconnected-(JP6-Pad17)") (class "Default")
      (node (ref "JP6") (pin "17") (pinfunction "17_17") (pintype "passive"))
    )
    (net (code "162") (name "unconnected-(JP6-Pad18)") (class "Default")
      (node (ref "JP6") (pin "18") (pinfunction "18_18") (pintype "passive"))
    )
    (net (code "163") (name "unconnected-(JP6-Pad19)") (class "Default")
      (node (ref "JP6") (pin "19") (pinfunction "19_19") (pintype "passive"))
    )
    (net (code "164") (name "unconnected-(JP6-Pad20)") (class "Default")
      (node (ref "JP6") (pin "20") (pinfunction "20_20") (pintype "passive"))
    )
    (net (code "165") (name "unconnected-(JP11-Pad3)") (class "Default")
      (node (ref "JP11") (pin "3") (pinfunction "3_3") (pintype "passive"))
    )
    (net (code "166") (name "unconnected-(JP11-Pad4)") (class "Default")
      (node (ref "JP11") (pin "4") (pinfunction "4_4") (pintype "passive"))
    )
    (net (code "167") (name "unconnected-(JP11-Pad5)") (class "Default")
      (node (ref "JP11") (pin "5") (pinfunction "5_5") (pintype "passive"))
    )
    (net (code "168") (name "unconnected-(JP11-Pad6)") (class "Default")
      (node (ref "JP11") (pin "6") (pinfunction "6_6") (pintype "passive"))
    )
    (net (code "169") (name "unconnected-(JP11-Pad7)") (class "Default")
      (node (ref "JP11") (pin "7") (pinfunction "7_7") (pintype "passive"))
    )
    (net (code "170") (name "unconnected-(JP11-Pad8)") (class "Default")
      (node (ref "JP11") (pin "8") (pinfunction "8_8") (pintype "passive"))
    )
    (net (code "171") (name "unconnected-(JP11-Pad9)") (class "Default")
      (node (ref "JP11") (pin "9") (pinfunction "9_9") (pintype "passive"))
    )
    (net (code "172") (name "unconnected-(JP11-Pad10)") (class "Default")
      (node (ref "JP11") (pin "10") (pinfunction "10_10") (pintype "passive"))
    )
    (net (code "173") (name "unconnected-(JP11-Pad11)") (class "Default")
      (node (ref "JP11") (pin "11") (pinfunction "11_11") (pintype "passive"))
    )
    (net (code "174") (name "unconnected-(JP11-Pad12)") (class "Default")
      (node (ref "JP11") (pin "12") (pinfunction "12_12") (pintype "passive"))
    )
    (net (code "175") (name "unconnected-(JP11-Pad13)") (class "Default")
      (node (ref "JP11") (pin "13") (pinfunction "13_13") (pintype "passive"))
    )
    (net (code "176") (name "unconnected-(JP11-Pad14)") (class "Default")
      (node (ref "JP11") (pin "14") (pinfunction "14_14") (pintype "passive"))
    )
    (net (code "177") (name "unconnected-(JP11-Pad15)") (class "Default")
      (node (ref "JP11") (pin "15") (pinfunction "15_15") (pintype "passive"))
    )
    (net (code "178") (name "unconnected-(JP11-Pad16)") (class "Default")
      (node (ref "JP11") (pin "16") (pinfunction "16_16") (pintype "passive"))
    )
    (net (code "179") (name "unconnected-(JP11-Pad17)") (class "Default")
      (node (ref "JP11") (pin "17") (pinfunction "17_17") (pintype "passive"))
    )
    (net (code "180") (name "unconnected-(JP11-Pad18)") (class "Default")
      (node (ref "JP11") (pin "18") (pinfunction "18_18") (pintype "passive"))
    )
    (net (code "181") (name "unconnected-(JP11-Pad19)") (class "Default")
      (node (ref "JP11") (pin "19") (pinfunction "19_19") (pintype "passive"))
    )
    (net (code "182") (name "unconnected-(JP11-Pad20)") (class "Default")
      (node (ref "JP11") (pin "20") (pinfunction "20_20") (pintype "passive"))
    )
    (net (code "183") (name "unconnected-(M1-A4-PadJ2.1)") (class "Default")
      (node (ref "M1") (pin "J2.1") (pinfunction "A4_J2.1") (pintype "bidirectional"))
    )
    (net (code "184") (name "unconnected-(M1-A5-PadJ2.2)") (class "Default")
      (node (ref "M1") (pin "J2.2") (pinfunction "A5_J2.2") (pintype "bidirectional"))
    )
    (net (code "185") (name "unconnected-(U$5-NC-Pad1)") (class "Default")
      (node (ref "U$5") (pin "1") (pinfunction "NC_1") (pintype "bidirectional"))
    )
    (net (code "186") (name "unconnected-(U$5-NC1-Pad20)") (class "Default")
      (node (ref "U$5") (pin "20") (pinfunction "NC1_20") (pintype "bidirectional"))
    )
    (net (code "187") (name "unconnected-(U$6-NC-Pad1)") (class "Default")
      (node (ref "U$6") (pin "1") (pinfunction "NC_1") (pintype "bidirectional"))
    )
    (net (code "188") (name "unconnected-(U$6-NC1-Pad20)") (class "Default")
      (node (ref "U$6") (pin "20") (pinfunction "NC1_20") (pintype "bidirectional"))
    )
    (net (code "189") (name "unconnected-(VCC_5V-Pad1)") (class "Default")
      (node (ref "VCC_5V") (pin "1") (pinfunction "1_1") (pintype "passive"))
    )
    (net (code "190") (name "unconnected-(VCC_5V-Pad3)") (class "Default")
      (node (ref "VCC_5V") (pin "3") (pinfunction "3_3") (pintype "passive"))
    )
    (net (code "191") (name "unconnected-(VCC_5V-Pad5)") (class "Default")
      (node (ref "VCC_5V") (pin "5") (pinfunction "5_5") (pintype "passive"))
    )
    (net (code "192") (name "unconnected-(VCC_5V-Pad7)") (class "Default")
      (node (ref "VCC_5V") (pin "7") (pinfunction "7_7") (pintype "passive"))
    )
    (net (code "193") (name "unconnected-(VCC_5V-Pad9)") (class "Default")
      (node (ref "VCC_5V") (pin "9") (pinfunction "9_9") (pintype "passive"))
    )
    (net (code "194") (name "unconnected-(VCC_5V-Pad11)") (class "Default")
      (node (ref "VCC_5V") (pin "11") (pinfunction "11_11") (pintype "passive"))
    )
    (net (code "195") (name "unconnected-(VCC_5V-Pad13)") (class "Default")
      (node (ref "VCC_5V") (pin "13") (pinfunction "13_13") (pintype "passive"))
    )
    (net (code "196") (name "unconnected-(VCC_5V-Pad15)") (class "Default")
      (node (ref "VCC_5V") (pin "15") (pinfunction "15_15") (pintype "passive"))
    )
    (net (code "197") (name "unconnected-(VCC_5V-Pad17)") (class "Default")
      (node (ref "VCC_5V") (pin "17") (pinfunction "17_17") (pintype "passive"))
    )
    (net (code "198") (name "unconnected-(VCC_5V-Pad19)") (class "Default")
      (node (ref "VCC_5V") (pin "19") (pinfunction "19_19") (pintype "passive"))
    )
  )
)
